# 12V_DCDC.net
KiCad netlist of a schematic drawn in Altium Designer
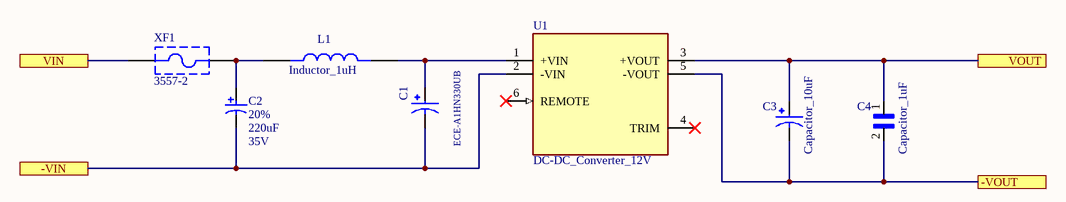
[diagram p0: 12V DCDC.SchDoc]

(export (version "E")
  (design (tool "Eeschema 10.0.6"))
  (components
    (comp (ref "C1")
      (value "ECE-A1HN330UB")
      (footprint "Capacitor_33uF")
      (description "Cap Aluminum 33uF 50V 20% (8 X 11.5mm) Radial 5mm 110mA 2000 hr 85°C Ammo Pack")
      (fields (field (name "MANUFACTURER") "Panasonic") (field (name "TOLERANCE") "20%"))
      (libsource (lib "Schlib1") (part "Capacitor_33uF"))
    )
    (comp (ref "C2")
      (value "220uF")
      (footprint "NicCap_10x12.5")
      (fields
        (field (name "TOLERANCE") "20%")
        (field (name "VOLTAGE") "35V")
        (field (name "Comment") "ESC227M035AH1AA")
      )
      (libsource (lib "ESE)") (part "NIC-CAP-P-2"))
    )
    (comp (ref "C3")
      (value "Capacitor_10uF")
      (footprint "Capacitor_10uF")
      (description "Cap Aluminum 10uF 50V 20% (6.3 X 5mm) Radial 2.5mm 35mA 1000 hr 85°C Bulk")
      (fields
        (field (name "MANUFACTURER") "Panasonic")
        (field (name "MANUFACTURER PART NUMBER") "ECE-A1HKS100")
      )
      (libsource (lib "Schlib1") (part "Capacitor_10uF"))
    )
    (comp (ref "C4")
      (value "Capacitor_1uF")
      (footprint "Capacitor_1uF")
      (description "Cap Ceramic 1uF 50V X5R 10% Radial 5mm 85C Ammo")
      (fields
        (field (name "MANUFACTURER") "TDK")
        (field (name "MANUFACTURER PART NUMBER") "FG28X5R1H105KRT06")
      )
      (libsource (lib "Schlib1") (part "Capacitor_1uF"))
    )
    (comp (ref "L1")
      (value "Inductor_1uH")
      (footprint "Inductor_1uH")
      (description "Inductor Power Drum Core 1uH 20% 7.96MHz 20Q-Factor Ferrite 3.5A 0.013Ohm DCR RDL Automotive Box")
      (fields
        (field (name "MANUFACTURER") "Abracon")
        (field (name "MANUFACTURER PART NUMBER") "AIUR-03-1R0M")
      )
      (libsource (lib "Schlib1") (part "Inductor_1uH"))
    )
    (comp (ref "U1")
      (value "DC-DC_Converter_12V")
      (footprint "DC-DC_Converter_12V")
      (description "Isolated Module DC DC Converter 1 Output 12V - - 2.5A 9V - 36V Input")
      (libsource (lib "Schlib1") (part "DC-DC_Converter_12V"))
    )
    (comp (ref "XF1")
      (value "3557-2")
      (footprint "KSTN-3557-2")
      (description "Fuse Holder; Auto; 2 in1 Blade; THM; 1 Fuse; Vertical; 30 Amps; ATO/ATC")
      (libsource (lib "ESE)") (part "FUSE_HOLDER-4"))
    )
  )
  (nets
    (net (code "1") (name "/-VIN") (class "Default")
      (node (ref "C1") (pin "N") (pinfunction "N_N") (pintype "passive"))
      (node (ref "C2") (pin "2") (pinfunction "2_2") (pintype "passive"))
      (node (ref "U1") (pin "2") (pinfunction "-VIN_2") (pintype "power_in"))
    )
    (net (code "2") (name "/-VOUT") (class "Default")
      (node (ref "C3") (pin "N") (pinfunction "N_N") (pintype "passive"))
      (node (ref "C4") (pin "2") (pinfunction "2_2") (pintype "passive"))
      (node (ref "U1") (pin "5") (pinfunction "-VOUT_5") (pintype "power_in"))
    )
    (net (code "3") (name "/VIN") (class "Default")
      (node (ref "XF1") (pin "1") (pinfunction "1_1") (pintype "passive"))
    )
    (net (code "4") (name "/VOUT") (class "Default")
      (node (ref "C3") (pin "P") (pinfunction "P_P") (pintype "passive"))
      (node (ref "C4") (pin "1") (pinfunction "1_1") (pintype "passive"))
      (node (ref "U1") (pin "3") (pinfunction "+VOUT_3") (pintype "power_in"))
    )
    (net (code "5") (name "Net-(C2-Pad1)") (class "Default")
      (node (ref "C2") (pin "1") (pinfunction "1_1") (pintype "passive"))
      (node (ref "L1") (pin "1") (pinfunction "1_1") (pintype "passive"))
      (node (ref "XF1") (pin "2") (pinfunction "2_2") (pintype "passive"))
    )
    (net (code "6") (name "Net-(U1-+VIN)") (class "Default")
      (node (ref "C1") (pin "P") (pinfunction "P_P") (pintype "passive"))
      (node (ref "L1") (pin "2") (pinfunction "2_2") (pintype "passive"))
      (node (ref "U1") (pin "1") (pinfunction "+VIN_1") (pintype "power_in"))
    )
    (net (code "7") (name "unconnected-(U1-REMOTE-Pad6)") (class "Default")
      (node (ref "U1") (pin "6") (pinfunction "REMOTE_6") (pintype "input+no_connect"))
    )
    (net (code "8") (name "unconnected-(U1-TRIM-Pad4)") (class "Default")
      (node (ref "U1") (pin "4") (pinfunction "TRIM_4") (pintype "passive+no_connect"))
    )
  )
)
